# LCD.net
KiCad netlist of a schematic drawn in Altium Designer
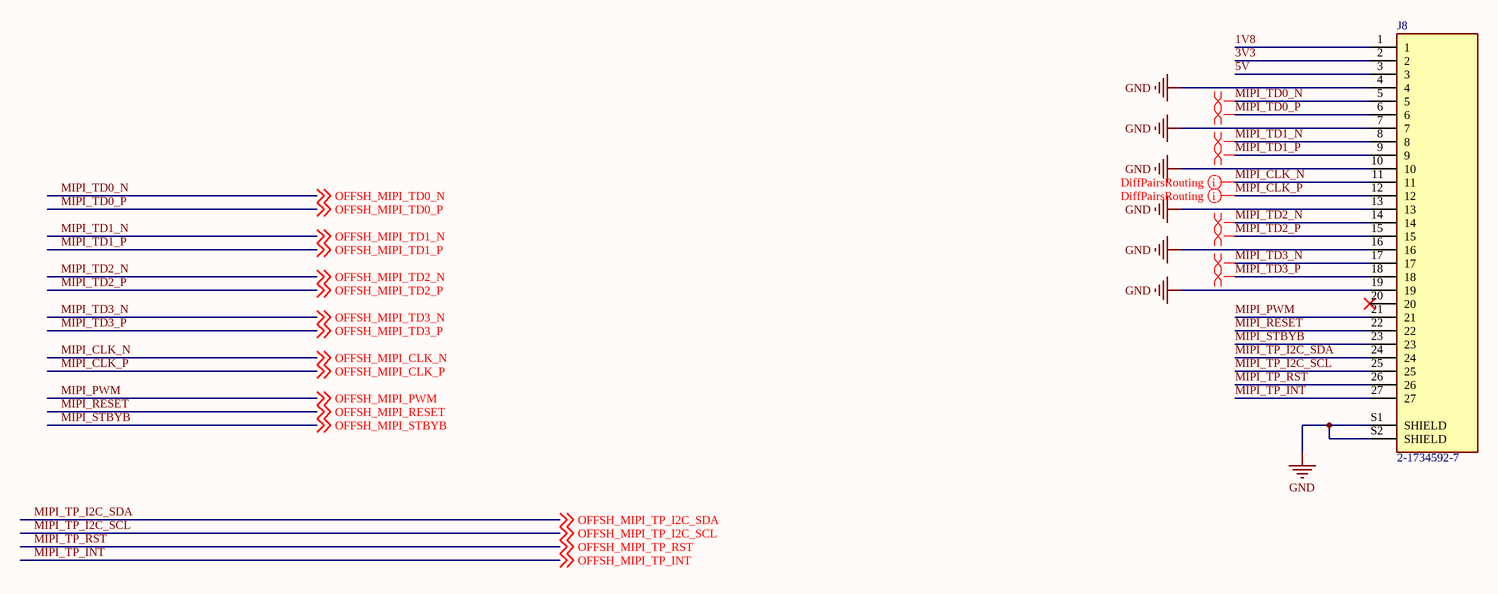
[diagram p0: LCD.SchDoc]

(export (version "E")
  (design (tool "Eeschema 10.0.6"))
  (components
    (comp (ref "J8")
      (value "2-1734592-7")
      (footprint "FPC_27pin_C:TE_2-1734592-7")
      (libsource (lib "FPC_27pin_C") (part "2-1734592-7"))
    )
  )
  (nets
    (net (code "1") (name "/1V8") (class "Default")
      (node (ref "J8") (pin "1") (pinfunction "1_1") (pintype "passive"))
    )
    (net (code "2") (name "/3V3") (class "Default")
      (node (ref "J8") (pin "2") (pinfunction "2_2") (pintype "passive"))
    )
    (net (code "3") (name "/5V") (class "Default")
      (node (ref "J8") (pin "3") (pinfunction "3_3") (pintype "passive"))
    )
    (net (code "4") (name "GND") (class "Default")
      (node (ref "J8") (pin "10") (pinfunction "10_10") (pintype "passive"))
      (node (ref "J8") (pin "13") (pinfunction "13_13") (pintype "passive"))
      (node (ref "J8") (pin "16") (pinfunction "16_16") (pintype "passive"))
      (node (ref "J8") (pin "19") (pinfunction "19_19") (pintype "passive"))
      (node (ref "J8") (pin "4") (pinfunction "4_4") (pintype "passive"))
      (node (ref "J8") (pin "7") (pinfunction "7_7") (pintype "passive"))
      (node (ref "J8") (pin "S1") (pinfunction "SHIELD_S1") (pintype "passive"))
      (node (ref "J8") (pin "S2") (pinfunction "SHIELD_S2") (pintype "passive"))
    )
    (net (code "5") (name "OFFSH_MIPI_CLK_N") (class "Default")
      (node (ref "J8") (pin "11") (pinfunction "11_11") (pintype "passive"))
    )
    (net (code "6") (name "OFFSH_MIPI_CLK_P") (class "Default")
      (node (ref "J8") (pin "12") (pinfunction "12_12") (pintype "passive"))
    )
    (net (code "7") (name "OFFSH_MIPI_PWM") (class "Default")
      (node (ref "J8") (pin "21") (pinfunction "21_21") (pintype "passive"))
    )
    (net (code "8") (name "OFFSH_MIPI_RESET") (class "Default")
      (node (ref "J8") (pin "22") (pinfunction "22_22") (pintype "passive"))
    )
    (net (code "9") (name "OFFSH_MIPI_STBYB") (class "Default")
      (node (ref "J8") (pin "23") (pinfunction "23_23") (pintype "passive"))
    )
    (net (code "10") (name "OFFSH_MIPI_TD0_N") (class "Default")
      (node (ref "J8") (pin "5") (pinfunction "5_5") (pintype "passive"))
    )
    (net (code "11") (name "OFFSH_MIPI_TD0_P") (class "Default")
      (node (ref "J8") (pin "6") (pinfunction "6_6") (pintype "passive"))
    )
    (net (code "12") (name "OFFSH_MIPI_TD1_N") (class "Default")
      (node (ref "J8") (pin "8") (pinfunction "8_8") (pintype "passive"))
    )
    (net (code "13") (name "OFFSH_MIPI_TD1_P") (class "Default")
      (node (ref "J8") (pin "9") (pinfunction "9_9") (pintype "passive"))
    )
    (net (code "14") (name "OFFSH_MIPI_TD2_N") (class "Default")
      (node (ref "J8") (pin "14") (pinfunction "14_14") (pintype "passive"))
    )
    (net (code "15") (name "OFFSH_MIPI_TD2_P") (class "Default")
      (node (ref "J8") (pin "15") (pinfunction "15_15") (pintype "passive"))
    )
    (net (code "16") (name "OFFSH_MIPI_TD3_N") (class "Default")
      (node (ref "J8") (pin "17") (pinfunction "17_17") (pintype "passive"))
    )
    (net (code "17") (name "OFFSH_MIPI_TD3_P") (class "Default")
      (node (ref "J8") (pin "18") (pinfunction "18_18") (pintype "passive"))
    )
    (net (code "18") (name "OFFSH_MIPI_TP_I2C_SCL") (class "Default")
      (node (ref "J8") (pin "25") (pinfunction "25_25") (pintype "passive"))
    )
    (net (code "19") (name "OFFSH_MIPI_TP_I2C_SDA") (class "Default")
      (node (ref "J8") (pin "24") (pinfunction "24_24") (pintype "passive"))
    )
    (net (code "20") (name "OFFSH_MIPI_TP_INT") (class "Default")
      (node (ref "J8") (pin "27") (pinfunction "27_27") (pintype "passive"))
    )
    (net (code "21") (name "OFFSH_MIPI_TP_RST") (class "Default")
      (node (ref "J8") (pin "26") (pinfunction "26_26") (pintype "passive"))
    )
    (net (code "22") (name "unconnected-(J8-Pad20)") (class "Default")
      (node (ref "J8") (pin "20") (pinfunction "20_20") (pintype "passive+no_connect"))
    )
  )
)
